# main_2.net
KiCad netlist of a schematic drawn in Altium Designer
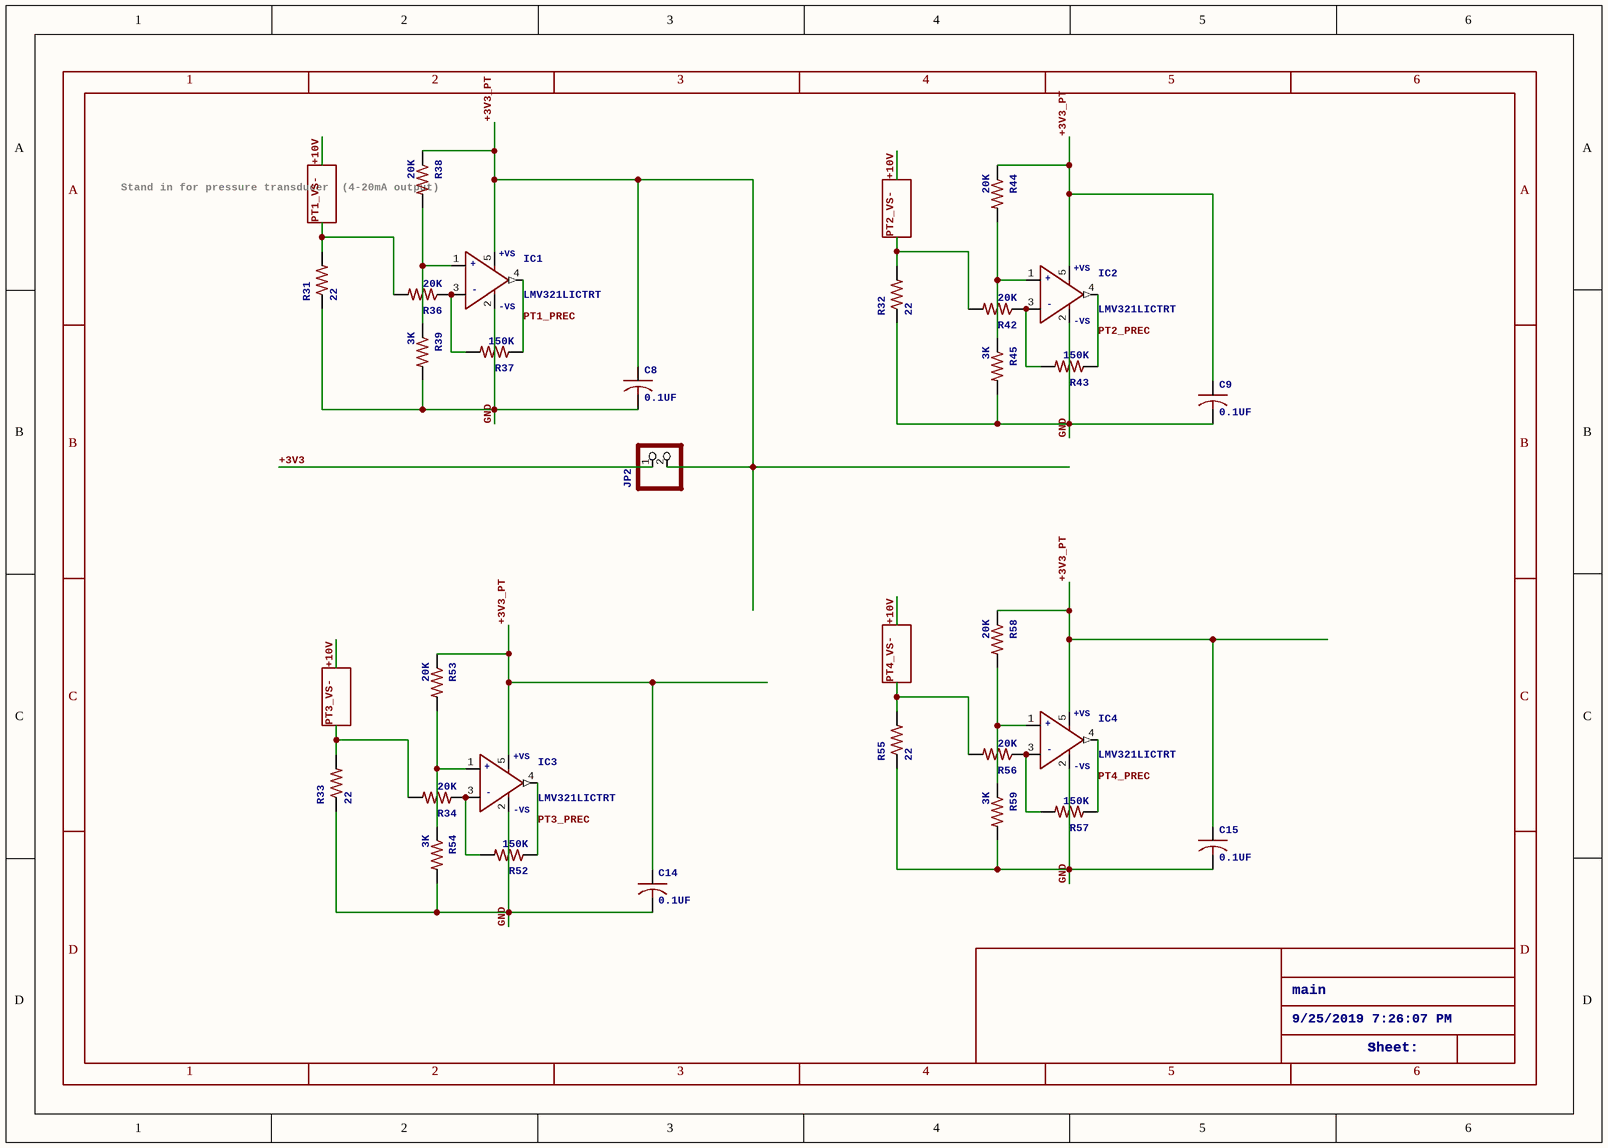
[diagram p0: main_2.SchDoc]

(export (version "E")
  (design (tool "Eeschema 10.0.6"))
  (components
    (comp (ref "C8")
      (value "0.1UF")
      (footprint "C0805")
      (description "CAPACITOR, American symbol")
      (libsource (lib "rcl") (part "C-USC0805"))
    )
    (comp (ref "C9")
      (value "0.1UF")
      (footprint "C0805")
      (description "CAPACITOR, American symbol")
      (libsource (lib "rcl") (part "C-USC0805"))
    )
    (comp (ref "C14")
      (value "0.1UF")
      (footprint "C0805")
      (description "CAPACITOR, American symbol")
      (libsource (lib "rcl") (part "C-USC0805"))
    )
    (comp (ref "C15")
      (value "0.1UF")
      (footprint "C0805")
      (description "CAPACITOR, American symbol")
      (libsource (lib "rcl") (part "C-USC0805"))
    )
    (comp (ref "IC1")
      (value "LMV321LICTRT")
      (footprint "SOT23-5")
      (fields
        (field (name "MF") "ALTERA CORPORATION")
        (field (name "MPN") "AD8065ARTZ-REEL7")
        (field (name "+") "+")
        (field (name "-") "-")
        (field (name "+VS") "+VS")
        (field (name "-VS") "-VS")
        (field (name "LIBRARYNAME") "st-microelectronics-extra")
      )
      (libsource (lib "st-microelectronics-extra") (part "LMV321LICTRT"))
    )
    (comp (ref "IC2")
      (value "LMV321LICTRT")
      (footprint "SOT23-5")
      (fields
        (field (name "MF") "ALTERA CORPORATION")
        (field (name "MPN") "AD8065ARTZ-REEL7")
        (field (name "+") "+")
        (field (name "-") "-")
        (field (name "+VS") "+VS")
        (field (name "-VS") "-VS")
        (field (name "LIBRARYNAME") "st-microelectronics-extra")
      )
      (libsource (lib "st-microelectronics-extra") (part "LMV321LICTRT"))
    )
    (comp (ref "IC3")
      (value "LMV321LICTRT")
      (footprint "SOT23-5")
      (fields
        (field (name "MF") "ALTERA CORPORATION")
        (field (name "MPN") "AD8065ARTZ-REEL7")
        (field (name "+") "+")
        (field (name "-") "-")
        (field (name "+VS") "+VS")
        (field (name "-VS") "-VS")
        (field (name "LIBRARYNAME") "st-microelectronics-extra")
      )
      (libsource (lib "st-microelectronics-extra") (part "LMV321LICTRT"))
    )
    (comp (ref "IC4")
      (value "LMV321LICTRT")
      (footprint "SOT23-5")
      (fields
        (field (name "MF") "ALTERA CORPORATION")
        (field (name "MPN") "AD8065ARTZ-REEL7")
        (field (name "+") "+")
        (field (name "-") "-")
        (field (name "+VS") "+VS")
        (field (name "-VS") "-VS")
        (field (name "LIBRARYNAME") "st-microelectronics-extra")
      )
      (libsource (lib "st-microelectronics-extra") (part "LMV321LICTRT"))
    )
    (comp (ref "JP2")
      (value "PINHD-1X2")
      (footprint "1X02")
      (description "PIN HEADER")
      (fields (field (name "LIBRARYNAME") "pinhead"))
      (libsource (lib "pinhead") (part "PINHD-1X2"))
    )
    (comp (ref "R31")
      (value "22")
      (footprint "R0805")
      (description "RESISTOR, American symbol")
      (libsource (lib "rcl") (part "R-US_R0805"))
    )
    (comp (ref "R32")
      (value "22")
      (footprint "R0805")
      (description "RESISTOR, American symbol")
      (libsource (lib "rcl") (part "R-US_R0805"))
    )
    (comp (ref "R33")
      (value "22")
      (footprint "R0805")
      (description "RESISTOR, American symbol")
      (libsource (lib "rcl") (part "R-US_R0805"))
    )
    (comp (ref "R34")
      (value "20K")
      (footprint "R0805")
      (description "RESISTOR, American symbol")
      (libsource (lib "rcl") (part "R-US_R0805"))
    )
    (comp (ref "R36")
      (value "20K")
      (footprint "R0805")
      (description "RESISTOR, American symbol")
      (libsource (lib "rcl") (part "R-US_R0805"))
    )
    (comp (ref "R37")
      (value "150K")
      (footprint "R0805")
      (description "RESISTOR, American symbol")
      (libsource (lib "rcl") (part "R-US_R0805"))
    )
    (comp (ref "R38")
      (value "20K")
      (footprint "R0805")
      (description "RESISTOR, American symbol")
      (libsource (lib "rcl") (part "R-US_R0805"))
    )
    (comp (ref "R39")
      (value "3K")
      (footprint "R0805")
      (description "RESISTOR, American symbol")
      (libsource (lib "rcl") (part "R-US_R0805"))
    )
    (comp (ref "R42")
      (value "20K")
      (footprint "R0805")
      (description "RESISTOR, American symbol")
      (libsource (lib "rcl") (part "R-US_R0805"))
    )
    (comp (ref "R43")
      (value "150K")
      (footprint "R0805")
      (description "RESISTOR, American symbol")
      (libsource (lib "rcl") (part "R-US_R0805"))
    )
    (comp (ref "R44")
      (value "20K")
      (footprint "R0805")
      (description "RESISTOR, American symbol")
      (libsource (lib "rcl") (part "R-US_R0805"))
    )
    (comp (ref "R45")
      (value "3K")
      (footprint "R0805")
      (description "RESISTOR, American symbol")
      (libsource (lib "rcl") (part "R-US_R0805"))
    )
    (comp (ref "R52")
      (value "150K")
      (footprint "R0805")
      (description "RESISTOR, American symbol")
      (libsource (lib "rcl") (part "R-US_R0805"))
    )
    (comp (ref "R53")
      (value "20K")
      (footprint "R0805")
      (description "RESISTOR, American symbol")
      (libsource (lib "rcl") (part "R-US_R0805"))
    )
    (comp (ref "R54")
      (value "3K")
      (footprint "R0805")
      (description "RESISTOR, American symbol")
      (libsource (lib "rcl") (part "R-US_R0805"))
    )
    (comp (ref "R55")
      (value "22")
      (footprint "R0805")
      (description "RESISTOR, American symbol")
      (libsource (lib "rcl") (part "R-US_R0805"))
    )
    (comp (ref "R56")
      (value "20K")
      (footprint "R0805")
      (description "RESISTOR, American symbol")
      (libsource (lib "rcl") (part "R-US_R0805"))
    )
    (comp (ref "R57")
      (value "150K")
      (footprint "R0805")
      (description "RESISTOR, American symbol")
      (libsource (lib "rcl") (part "R-US_R0805"))
    )
    (comp (ref "R58")
      (value "20K")
      (footprint "R0805")
      (description "RESISTOR, American symbol")
      (libsource (lib "rcl") (part "R-US_R0805"))
    )
    (comp (ref "R59")
      (value "3K")
      (footprint "R0805")
      (description "RESISTOR, American symbol")
      (libsource (lib "rcl") (part "R-US_R0805"))
    )
  )
  (nets
    (net (code "1") (name "/+3V3") (class "Default")
      (node (ref "JP2") (pin "1") (pinfunction "1_1") (pintype "passive"))
    )
    (net (code "2") (name "/+3V3_PT") (class "Default")
      (node (ref "C14") (pin "1") (pinfunction "1_1") (pintype "passive"))
      (node (ref "C15") (pin "1") (pinfunction "1_1") (pintype "passive"))
      (node (ref "C8") (pin "1") (pinfunction "1_1") (pintype "passive"))
      (node (ref "C9") (pin "1") (pinfunction "1_1") (pintype "passive"))
      (node (ref "IC1") (pin "5") (pinfunction "+VS_5") (pintype "passive"))
      (node (ref "IC2") (pin "5") (pinfunction "+VS_5") (pintype "passive"))
      (node (ref "IC3") (pin "5") (pinfunction "+VS_5") (pintype "passive"))
      (node (ref "IC4") (pin "5") (pinfunction "+VS_5") (pintype "passive"))
      (node (ref "JP2") (pin "2") (pinfunction "2_2") (pintype "passive"))
      (node (ref "R38") (pin "1") (pinfunction "1_1") (pintype "passive"))
      (node (ref "R44") (pin "1") (pinfunction "1_1") (pintype "passive"))
      (node (ref "R53") (pin "1") (pinfunction "1_1") (pintype "passive"))
      (node (ref "R58") (pin "1") (pinfunction "1_1") (pintype "passive"))
    )
    (net (code "4") (name "/GND") (class "Default")
      (node (ref "C14") (pin "2") (pinfunction "2_2") (pintype "passive"))
      (node (ref "C15") (pin "2") (pinfunction "2_2") (pintype "passive"))
      (node (ref "C8") (pin "2") (pinfunction "2_2") (pintype "passive"))
      (node (ref "C9") (pin "2") (pinfunction "2_2") (pintype "passive"))
      (node (ref "IC1") (pin "2") (pinfunction "-VS_2") (pintype "passive"))
      (node (ref "IC2") (pin "2") (pinfunction "-VS_2") (pintype "passive"))
      (node (ref "IC3") (pin "2") (pinfunction "-VS_2") (pintype "passive"))
      (node (ref "IC4") (pin "2") (pinfunction "-VS_2") (pintype "passive"))
      (node (ref "R31") (pin "1") (pinfunction "1_1") (pintype "passive"))
      (node (ref "R32") (pin "1") (pinfunction "1_1") (pintype "passive"))
      (node (ref "R33") (pin "1") (pinfunction "1_1") (pintype "passive"))
      (node (ref "R39") (pin "2") (pinfunction "2_2") (pintype "passive"))
      (node (ref "R45") (pin "2") (pinfunction "2_2") (pintype "passive"))
      (node (ref "R54") (pin "2") (pinfunction "2_2") (pintype "passive"))
      (node (ref "R55") (pin "1") (pinfunction "1_1") (pintype "passive"))
      (node (ref "R59") (pin "2") (pinfunction "2_2") (pintype "passive"))
    )
    (net (code "5") (name "/PT1_PREC") (class "Default")
      (node (ref "IC1") (pin "4") (pinfunction "OUT_4") (pintype "output"))
      (node (ref "R37") (pin "1") (pinfunction "1_1") (pintype "passive"))
    )
    (net (code "6") (name "/PT1_VS-") (class "Default")
      (node (ref "R31") (pin "2") (pinfunction "2_2") (pintype "passive"))
      (node (ref "R36") (pin "2") (pinfunction "2_2") (pintype "passive"))
    )
    (net (code "7") (name "/PT2_PREC") (class "Default")
      (node (ref "IC2") (pin "4") (pinfunction "OUT_4") (pintype "output"))
      (node (ref "R43") (pin "1") (pinfunction "1_1") (pintype "passive"))
    )
    (net (code "8") (name "/PT2_VS-") (class "Default")
      (node (ref "R32") (pin "2") (pinfunction "2_2") (pintype "passive"))
      (node (ref "R42") (pin "2") (pinfunction "2_2") (pintype "passive"))
    )
    (net (code "9") (name "/PT3_PREC") (class "Default")
      (node (ref "IC3") (pin "4") (pinfunction "OUT_4") (pintype "output"))
      (node (ref "R52") (pin "1") (pinfunction "1_1") (pintype "passive"))
    )
    (net (code "10") (name "/PT3_VS-") (class "Default")
      (node (ref "R33") (pin "2") (pinfunction "2_2") (pintype "passive"))
      (node (ref "R34") (pin "2") (pinfunction "2_2") (pintype "passive"))
    )
    (net (code "11") (name "/PT4_PREC") (class "Default")
      (node (ref "IC4") (pin "4") (pinfunction "OUT_4") (pintype "output"))
      (node (ref "R57") (pin "1") (pinfunction "1_1") (pintype "passive"))
    )
    (net (code "12") (name "/PT4_VS-") (class "Default")
      (node (ref "R55") (pin "2") (pinfunction "2_2") (pintype "passive"))
      (node (ref "R56") (pin "2") (pinfunction "2_2") (pintype "passive"))
    )
    (net (code "13") (name "Net-(IC1-IN+)") (class "Default")
      (node (ref "IC1") (pin "1") (pinfunction "IN+_1") (pintype "passive"))
      (node (ref "R38") (pin "2") (pinfunction "2_2") (pintype "passive"))
      (node (ref "R39") (pin "1") (pinfunction "1_1") (pintype "passive"))
    )
    (net (code "14") (name "Net-(IC1-IN-)") (class "Default")
      (node (ref "IC1") (pin "3") (pinfunction "IN-_3") (pintype "passive"))
      (node (ref "R36") (pin "1") (pinfunction "1_1") (pintype "passive"))
      (node (ref "R37") (pin "2") (pinfunction "2_2") (pintype "passive"))
    )
    (net (code "15") (name "Net-(IC2-IN+)") (class "Default")
      (node (ref "IC2") (pin "1") (pinfunction "IN+_1") (pintype "passive"))
      (node (ref "R44") (pin "2") (pinfunction "2_2") (pintype "passive"))
      (node (ref "R45") (pin "1") (pinfunction "1_1") (pintype "passive"))
    )
    (net (code "16") (name "Net-(IC2-IN-)") (class "Default")
      (node (ref "IC2") (pin "3") (pinfunction "IN-_3") (pintype "passive"))
      (node (ref "R42") (pin "1") (pinfunction "1_1") (pintype "passive"))
      (node (ref "R43") (pin "2") (pinfunction "2_2") (pintype "passive"))
    )
    (net (code "17") (name "Net-(IC3-IN+)") (class "Default")
      (node (ref "IC3") (pin "1") (pinfunction "IN+_1") (pintype "passive"))
      (node (ref "R53") (pin "2") (pinfunction "2_2") (pintype "passive"))
      (node (ref "R54") (pin "1") (pinfunction "1_1") (pintype "passive"))
    )
    (net (code "18") (name "Net-(IC3-IN-)") (class "Default")
      (node (ref "IC3") (pin "3") (pinfunction "IN-_3") (pintype "passive"))
      (node (ref "R34") (pin "1") (pinfunction "1_1") (pintype "passive"))
      (node (ref "R52") (pin "2") (pinfunction "2_2") (pintype "passive"))
    )
    (net (code "19") (name "Net-(IC4-IN+)") (class "Default")
      (node (ref "IC4") (pin "1") (pinfunction "IN+_1") (pintype "passive"))
      (node (ref "R58") (pin "2") (pinfunction "2_2") (pintype "passive"))
      (node (ref "R59") (pin "1") (pinfunction "1_1") (pintype "passive"))
    )
    (net (code "20") (name "Net-(IC4-IN-)") (class "Default")
      (node (ref "IC4") (pin "3") (pinfunction "IN-_3") (pintype "passive"))
      (node (ref "R56") (pin "1") (pinfunction "1_1") (pintype "passive"))
      (node (ref "R57") (pin "2") (pinfunction "2_2") (pintype "passive"))
    )
  )
)
